# SparkFun_LED_Array_8x7_Charlieplex.net
KiCad netlist of a schematic drawn in EAGLE
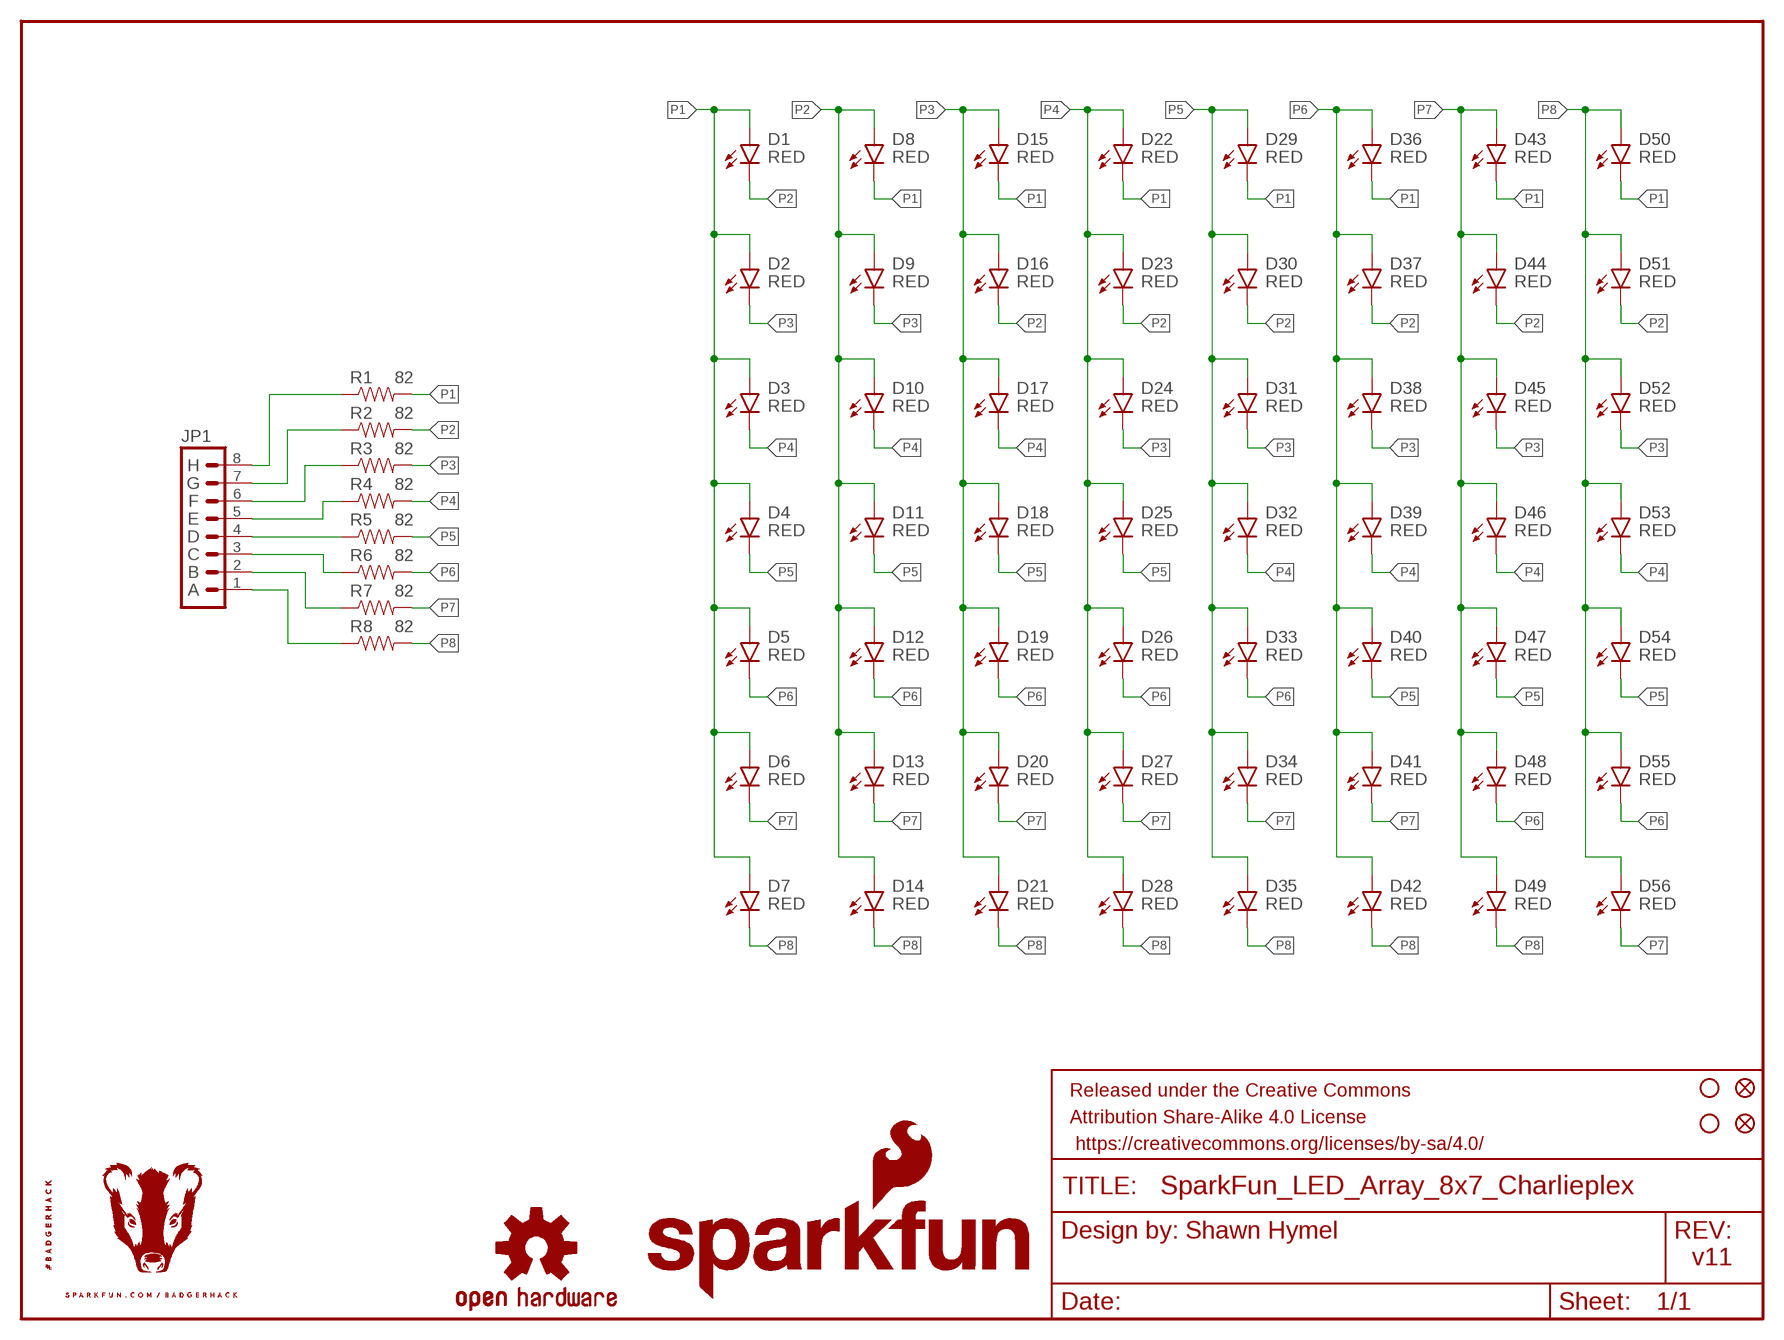
[diagram p0: schematic, sheet 1]

(export (version "E")
  (design (tool "Eeschema 10.0.6"))
  (components
    (comp (ref "D1")
      (value "RED")
      (footprint "eagle-import:LED-0603")
      (libsource (lib "eagle-import") (part "LED-RED0603"))
    )
    (comp (ref "D2")
      (value "RED")
      (footprint "eagle-import:LED-0603")
      (libsource (lib "eagle-import") (part "LED-RED0603"))
    )
    (comp (ref "D3")
      (value "RED")
      (footprint "eagle-import:LED-0603")
      (libsource (lib "eagle-import") (part "LED-RED0603"))
    )
    (comp (ref "D4")
      (value "RED")
      (footprint "eagle-import:LED-0603")
      (libsource (lib "eagle-import") (part "LED-RED0603"))
    )
    (comp (ref "D5")
      (value "RED")
      (footprint "eagle-import:LED-0603")
      (libsource (lib "eagle-import") (part "LED-RED0603"))
    )
    (comp (ref "D6")
      (value "RED")
      (footprint "eagle-import:LED-0603")
      (libsource (lib "eagle-import") (part "LED-RED0603"))
    )
    (comp (ref "D7")
      (value "RED")
      (footprint "eagle-import:LED-0603")
      (libsource (lib "eagle-import") (part "LED-RED0603"))
    )
    (comp (ref "D8")
      (value "RED")
      (footprint "eagle-import:LED-0603")
      (libsource (lib "eagle-import") (part "LED-RED0603"))
    )
    (comp (ref "D9")
      (value "RED")
      (footprint "eagle-import:LED-0603")
      (libsource (lib "eagle-import") (part "LED-RED0603"))
    )
    (comp (ref "D10")
      (value "RED")
      (footprint "eagle-import:LED-0603")
      (libsource (lib "eagle-import") (part "LED-RED0603"))
    )
    (comp (ref "D11")
      (value "RED")
      (footprint "eagle-import:LED-0603")
      (libsource (lib "eagle-import") (part "LED-RED0603"))
    )
    (comp (ref "D12")
      (value "RED")
      (footprint "eagle-import:LED-0603")
      (libsource (lib "eagle-import") (part "LED-RED0603"))
    )
    (comp (ref "D13")
      (value "RED")
      (footprint "eagle-import:LED-0603")
      (libsource (lib "eagle-import") (part "LED-RED0603"))
    )
    (comp (ref "D14")
      (value "RED")
      (footprint "eagle-import:LED-0603")
      (libsource (lib "eagle-import") (part "LED-RED0603"))
    )
    (comp (ref "D15")
      (value "RED")
      (footprint "eagle-import:LED-0603")
      (libsource (lib "eagle-import") (part "LED-RED0603"))
    )
    (comp (ref "D16")
      (value "RED")
      (footprint "eagle-import:LED-0603")
      (libsource (lib "eagle-import") (part "LED-RED0603"))
    )
    (comp (ref "D17")
      (value "RED")
      (footprint "eagle-import:LED-0603")
      (libsource (lib "eagle-import") (part "LED-RED0603"))
    )
    (comp (ref "D18")
      (value "RED")
      (footprint "eagle-import:LED-0603")
      (libsource (lib "eagle-import") (part "LED-RED0603"))
    )
    (comp (ref "D19")
      (value "RED")
      (footprint "eagle-import:LED-0603")
      (libsource (lib "eagle-import") (part "LED-RED0603"))
    )
    (comp (ref "D20")
      (value "RED")
      (footprint "eagle-import:LED-0603")
      (libsource (lib "eagle-import") (part "LED-RED0603"))
    )
    (comp (ref "D21")
      (value "RED")
      (footprint "eagle-import:LED-0603")
      (libsource (lib "eagle-import") (part "LED-RED0603"))
    )
    (comp (ref "D22")
      (value "RED")
      (footprint "eagle-import:LED-0603")
      (libsource (lib "eagle-import") (part "LED-RED0603"))
    )
    (comp (ref "D23")
      (value "RED")
      (footprint "eagle-import:LED-0603")
      (libsource (lib "eagle-import") (part "LED-RED0603"))
    )
    (comp (ref "D24")
      (value "RED")
      (footprint "eagle-import:LED-0603")
      (libsource (lib "eagle-import") (part "LED-RED0603"))
    )
    (comp (ref "D25")
      (value "RED")
      (footprint "eagle-import:LED-0603")
      (libsource (lib "eagle-import") (part "LED-RED0603"))
    )
    (comp (ref "D26")
      (value "RED")
      (footprint "eagle-import:LED-0603")
      (libsource (lib "eagle-import") (part "LED-RED0603"))
    )
    (comp (ref "D27")
      (value "RED")
      (footprint "eagle-import:LED-0603")
      (libsource (lib "eagle-import") (part "LED-RED0603"))
    )
    (comp (ref "D28")
      (value "RED")
      (footprint "eagle-import:LED-0603")
      (libsource (lib "eagle-import") (part "LED-RED0603"))
    )
    (comp (ref "D29")
      (value "RED")
      (footprint "eagle-import:LED-0603")
      (libsource (lib "eagle-import") (part "LED-RED0603"))
    )
    (comp (ref "D30")
      (value "RED")
      (footprint "eagle-import:LED-0603")
      (libsource (lib "eagle-import") (part "LED-RED0603"))
    )
    (comp (ref "D31")
      (value "RED")
      (footprint "eagle-import:LED-0603")
      (libsource (lib "eagle-import") (part "LED-RED0603"))
    )
    (comp (ref "D32")
      (value "RED")
      (footprint "eagle-import:LED-0603")
      (libsource (lib "eagle-import") (part "LED-RED0603"))
    )
    (comp (ref "D33")
      (value "RED")
      (footprint "eagle-import:LED-0603")
      (libsource (lib "eagle-import") (part "LED-RED0603"))
    )
    (comp (ref "D34")
      (value "RED")
      (footprint "eagle-import:LED-0603")
      (libsource (lib "eagle-import") (part "LED-RED0603"))
    )
    (comp (ref "D35")
      (value "RED")
      (footprint "eagle-import:LED-0603")
      (libsource (lib "eagle-import") (part "LED-RED0603"))
    )
    (comp (ref "D36")
      (value "RED")
      (footprint "eagle-import:LED-0603")
      (libsource (lib "eagle-import") (part "LED-RED0603"))
    )
    (comp (ref "D37")
      (value "RED")
      (footprint "eagle-import:LED-0603")
      (libsource (lib "eagle-import") (part "LED-RED0603"))
    )
    (comp (ref "D38")
      (value "RED")
      (footprint "eagle-import:LED-0603")
      (libsource (lib "eagle-import") (part "LED-RED0603"))
    )
    (comp (ref "D39")
      (value "RED")
      (footprint "eagle-import:LED-0603")
      (libsource (lib "eagle-import") (part "LED-RED0603"))
    )
    (comp (ref "D40")
      (value "RED")
      (footprint "eagle-import:LED-0603")
      (libsource (lib "eagle-import") (part "LED-RED0603"))
    )
    (comp (ref "D41")
      (value "RED")
      (footprint "eagle-import:LED-0603")
      (libsource (lib "eagle-import") (part "LED-RED0603"))
    )
    (comp (ref "D42")
      (value "RED")
      (footprint "eagle-import:LED-0603")
      (libsource (lib "eagle-import") (part "LED-RED0603"))
    )
    (comp (ref "D43")
      (value "RED")
      (footprint "eagle-import:LED-0603")
      (libsource (lib "eagle-import") (part "LED-RED0603"))
    )
    (comp (ref "D44")
      (value "RED")
      (footprint "eagle-import:LED-0603")
      (libsource (lib "eagle-import") (part "LED-RED0603"))
    )
    (comp (ref "D45")
      (value "RED")
      (footprint "eagle-import:LED-0603")
      (libsource (lib "eagle-import") (part "LED-RED0603"))
    )
    (comp (ref "D46")
      (value "RED")
      (footprint "eagle-import:LED-0603")
      (libsource (lib "eagle-import") (part "LED-RED0603"))
    )
    (comp (ref "D47")
      (value "RED")
      (footprint "eagle-import:LED-0603")
      (libsource (lib "eagle-import") (part "LED-RED0603"))
    )
    (comp (ref "D48")
      (value "RED")
      (footprint "eagle-import:LED-0603")
      (libsource (lib "eagle-import") (part "LED-RED0603"))
    )
    (comp (ref "D49")
      (value "RED")
      (footprint "eagle-import:LED-0603")
      (libsource (lib "eagle-import") (part "LED-RED0603"))
    )
    (comp (ref "D50")
      (value "RED")
      (footprint "eagle-import:LED-0603")
      (libsource (lib "eagle-import") (part "LED-RED0603"))
    )
    (comp (ref "D51")
      (value "RED")
      (footprint "eagle-import:LED-0603")
      (libsource (lib "eagle-import") (part "LED-RED0603"))
    )
    (comp (ref "D52")
      (value "RED")
      (footprint "eagle-import:LED-0603")
      (libsource (lib "eagle-import") (part "LED-RED0603"))
    )
    (comp (ref "D53")
      (value "RED")
      (footprint "eagle-import:LED-0603")
      (libsource (lib "eagle-import") (part "LED-RED0603"))
    )
    (comp (ref "D54")
      (value "RED")
      (footprint "eagle-import:LED-0603")
      (libsource (lib "eagle-import") (part "LED-RED0603"))
    )
    (comp (ref "D55")
      (value "RED")
      (footprint "eagle-import:LED-0603")
      (libsource (lib "eagle-import") (part "LED-RED0603"))
    )
    (comp (ref "D56")
      (value "RED")
      (footprint "eagle-import:LED-0603")
      (libsource (lib "eagle-import") (part "LED-RED0603"))
    )
    (comp (ref "FID1")
      (value "FIDUCIAL1X2")
      (footprint "eagle-import:FIDUCIAL-1X2")
      (libsource (lib "eagle-import") (part "FIDUCIAL1X2"))
    )
    (comp (ref "FID2")
      (value "FIDUCIAL1X2")
      (footprint "eagle-import:FIDUCIAL-1X2")
      (libsource (lib "eagle-import") (part "FIDUCIAL1X2"))
    )
    (comp (ref "FRAME1")
      (value "FRAME-LETTER")
      (footprint "eagle-import:CREATIVE_COMMONS")
      (fields
        (field (name "DESIGNER") "Shawn Hymel")
        (field (name "VERSION") "v11")
        (field (name "DESIGNER_1") "Shawn Hymel")
        (field (name "VERSION_1") "v11")
      )
      (libsource (lib "eagle-import") (part "FRAME-LETTER"))
    )
    (comp (ref "JP1")
      (value "M08LOCK_NO_SILK")
      (footprint "eagle-import:1X08_LOCK_NO_SILK")
      (libsource (lib "eagle-import") (part "M08LOCK_NO_SILK"))
    )
    (comp (ref "LOGO2")
      (value "OSHW-LOGOS")
      (footprint "eagle-import:OSHW-LOGO-S")
      (libsource (lib "eagle-import") (part "OSHW-LOGOS"))
    )
    (comp (ref "R1")
      (value "82")
      (footprint "eagle-import:0603-RES")
      (libsource (lib "eagle-import") (part "82OHM-1/10W-1%(0603)SMD"))
    )
    (comp (ref "R2")
      (value "82")
      (footprint "eagle-import:0603-RES")
      (libsource (lib "eagle-import") (part "82OHM-1/10W-1%(0603)SMD"))
    )
    (comp (ref "R3")
      (value "82")
      (footprint "eagle-import:0603-RES")
      (libsource (lib "eagle-import") (part "82OHM-1/10W-1%(0603)SMD"))
    )
    (comp (ref "R4")
      (value "82")
      (footprint "eagle-import:0603-RES")
      (libsource (lib "eagle-import") (part "82OHM-1/10W-1%(0603)SMD"))
    )
    (comp (ref "R5")
      (value "82")
      (footprint "eagle-import:0603-RES")
      (libsource (lib "eagle-import") (part "82OHM-1/10W-1%(0603)SMD"))
    )
    (comp (ref "R6")
      (value "82")
      (footprint "eagle-import:0603-RES")
      (libsource (lib "eagle-import") (part "82OHM-1/10W-1%(0603)SMD"))
    )
    (comp (ref "R7")
      (value "82")
      (footprint "eagle-import:0603-RES")
      (libsource (lib "eagle-import") (part "82OHM-1/10W-1%(0603)SMD"))
    )
    (comp (ref "R8")
      (value "82")
      (footprint "eagle-import:0603-RES")
      (libsource (lib "eagle-import") (part "82OHM-1/10W-1%(0603)SMD"))
    )
    (comp (ref "STANDOFF1")
      (value "STAND-OFF")
      (footprint "eagle-import:STAND-OFF")
      (libsource (lib "eagle-import") (part "STAND-OFF"))
    )
    (comp (ref "STANDOFF2")
      (value "STAND-OFF")
      (footprint "eagle-import:STAND-OFF")
      (libsource (lib "eagle-import") (part "STAND-OFF"))
    )
    (comp (ref "U$1")
      (value "SFE_LOGO_NAME_FLAME.1_INCH")
      (footprint "eagle-import:SFE_LOGO_NAME_FLAME_.1")
      (libsource (lib "eagle-import") (part "SFE_LOGO_NAME_FLAME.1_INCH"))
    )
    (comp (ref "U$2")
      (value "BADGERHACK_LOGODUMMY")
      (footprint "eagle-import:DUMMY")
      (libsource (lib "eagle-import") (part "BADGERHACK_LOGODUMMY"))
    )
  )
  (nets
    (net (code "1") (name "Net-(JP1-Pad1)") (class "Default")
      (node (ref "JP1") (pin "1") (pinfunction "1_1") (pintype "passive"))
      (node (ref "R8") (pin "1") (pinfunction "1_1") (pintype "passive"))
    )
    (net (code "2") (name "Net-(JP1-Pad2)") (class "Default")
      (node (ref "JP1") (pin "2") (pinfunction "2_2") (pintype "passive"))
      (node (ref "R7") (pin "1") (pinfunction "1_1") (pintype "passive"))
    )
    (net (code "3") (name "Net-(JP1-Pad3)") (class "Default")
      (node (ref "JP1") (pin "3") (pinfunction "3_3") (pintype "passive"))
      (node (ref "R6") (pin "1") (pinfunction "1_1") (pintype "passive"))
    )
    (net (code "4") (name "Net-(JP1-Pad4)") (class "Default")
      (node (ref "JP1") (pin "4") (pinfunction "4_4") (pintype "passive"))
      (node (ref "R5") (pin "1") (pinfunction "1_1") (pintype "passive"))
    )
    (net (code "5") (name "Net-(JP1-Pad5)") (class "Default")
      (node (ref "JP1") (pin "5") (pinfunction "5_5") (pintype "passive"))
      (node (ref "R4") (pin "1") (pinfunction "1_1") (pintype "passive"))
    )
    (net (code "6") (name "Net-(JP1-Pad6)") (class "Default")
      (node (ref "JP1") (pin "6") (pinfunction "6_6") (pintype "passive"))
      (node (ref "R3") (pin "1") (pinfunction "1_1") (pintype "passive"))
    )
    (net (code "7") (name "Net-(JP1-Pad7)") (class "Default")
      (node (ref "JP1") (pin "7") (pinfunction "7_7") (pintype "passive"))
      (node (ref "R2") (pin "1") (pinfunction "1_1") (pintype "passive"))
    )
    (net (code "8") (name "Net-(JP1-Pad8)") (class "Default")
      (node (ref "JP1") (pin "8") (pinfunction "8_8") (pintype "passive"))
      (node (ref "R1") (pin "1") (pinfunction "1_1") (pintype "passive"))
    )
    (net (code "9") (name "P1") (class "Default")
      (node (ref "D1") (pin "A") (pinfunction "A_A") (pintype "passive"))
      (node (ref "D15") (pin "C") (pinfunction "C_C") (pintype "passive"))
      (node (ref "D2") (pin "A") (pinfunction "A_A") (pintype "passive"))
      (node (ref "D22") (pin "C") (pinfunction "C_C") (pintype "passive"))
      (node (ref "D29") (pin "C") (pinfunction "C_C") (pintype "passive"))
      (node (ref "D3") (pin "A") (pinfunction "A_A") (pintype "passive"))
      (node (ref "D36") (pin "C") (pinfunction "C_C") (pintype "passive"))
      (node (ref "D4") (pin "A") (pinfunction "A_A") (pintype "passive"))
      (node (ref "D43") (pin "C") (pinfunction "C_C") (pintype "passive"))
      (node (ref "D5") (pin "A") (pinfunction "A_A") (pintype "passive"))
      (node (ref "D50") (pin "C") (pinfunction "C_C") (pintype "passive"))
      (node (ref "D6") (pin "A") (pinfunction "A_A") (pintype "passive"))
      (node (ref "D7") (pin "A") (pinfunction "A_A") (pintype "passive"))
      (node (ref "D8") (pin "C") (pinfunction "C_C") (pintype "passive"))
      (node (ref "R1") (pin "2") (pinfunction "2_2") (pintype "passive"))
    )
    (net (code "10") (name "P2") (class "Default")
      (node (ref "D1") (pin "C") (pinfunction "C_C") (pintype "passive"))
      (node (ref "D10") (pin "A") (pinfunction "A_A") (pintype "passive"))
      (node (ref "D11") (pin "A") (pinfunction "A_A") (pintype "passive"))
      (node (ref "D12") (pin "A") (pinfunction "A_A") (pintype "passive"))
      (node (ref "D13") (pin "A") (pinfunction "A_A") (pintype "passive"))
      (node (ref "D14") (pin "A") (pinfunction "A_A") (pintype "passive"))
      (node (ref "D16") (pin "C") (pinfunction "C_C") (pintype "passive"))
      (node (ref "D23") (pin "C") (pinfunction "C_C") (pintype "passive"))
      (node (ref "D30") (pin "C") (pinfunction "C_C") (pintype "passive"))
      (node (ref "D37") (pin "C") (pinfunction "C_C") (pintype "passive"))
      (node (ref "D44") (pin "C") (pinfunction "C_C") (pintype "passive"))
      (node (ref "D51") (pin "C") (pinfunction "C_C") (pintype "passive"))
      (node (ref "D8") (pin "A") (pinfunction "A_A") (pintype "passive"))
      (node (ref "D9") (pin "A") (pinfunction "A_A") (pintype "passive"))
      (node (ref "R2") (pin "2") (pinfunction "2_2") (pintype "passive"))
    )
    (net (code "11") (name "P3") (class "Default")
      (node (ref "D15") (pin "A") (pinfunction "A_A") (pintype "passive"))
      (node (ref "D16") (pin "A") (pinfunction "A_A") (pintype "passive"))
      (node (ref "D17") (pin "A") (pinfunction "A_A") (pintype "passive"))
      (node (ref "D18") (pin "A") (pinfunction "A_A") (pintype "passive"))
      (node (ref "D19") (pin "A") (pinfunction "A_A") (pintype "passive"))
      (node (ref "D2") (pin "C") (pinfunction "C_C") (pintype "passive"))
      (node (ref "D20") (pin "A") (pinfunction "A_A") (pintype "passive"))
      (node (ref "D21") (pin "A") (pinfunction "A_A") (pintype "passive"))
      (node (ref "D24") (pin "C") (pinfunction "C_C") (pintype "passive"))
      (node (ref "D31") (pin "C") (pinfunction "C_C") (pintype "passive"))
      (node (ref "D38") (pin "C") (pinfunction "C_C") (pintype "passive"))
      (node (ref "D45") (pin "C") (pinfunction "C_C") (pintype "passive"))
      (node (ref "D52") (pin "C") (pinfunction "C_C") (pintype "passive"))
      (node (ref "D9") (pin "C") (pinfunction "C_C") (pintype "passive"))
      (node (ref "R3") (pin "2") (pinfunction "2_2") (pintype "passive"))
    )
    (net (code "12") (name "P4") (class "Default")
      (node (ref "D10") (pin "C") (pinfunction "C_C") (pintype "passive"))
      (node (ref "D17") (pin "C") (pinfunction "C_C") (pintype "passive"))
      (node (ref "D22") (pin "A") (pinfunction "A_A") (pintype "passive"))
      (node (ref "D23") (pin "A") (pinfunction "A_A") (pintype "passive"))
      (node (ref "D24") (pin "A") (pinfunction "A_A") (pintype "passive"))
      (node (ref "D25") (pin "A") (pinfunction "A_A") (pintype "passive"))
      (node (ref "D26") (pin "A") (pinfunction "A_A") (pintype "passive"))
      (node (ref "D27") (pin "A") (pinfunction "A_A") (pintype "passive"))
      (node (ref "D28") (pin "A") (pinfunction "A_A") (pintype "passive"))
      (node (ref "D3") (pin "C") (pinfunction "C_C") (pintype "passive"))
      (node (ref "D32") (pin "C") (pinfunction "C_C") (pintype "passive"))
      (node (ref "D39") (pin "C") (pinfunction "C_C") (pintype "passive"))
      (node (ref "D46") (pin "C") (pinfunction "C_C") (pintype "passive"))
      (node (ref "D53") (pin "C") (pinfunction "C_C") (pintype "passive"))
      (node (ref "R4") (pin "2") (pinfunction "2_2") (pintype "passive"))
    )
    (net (code "13") (name "P5") (class "Default")
      (node (ref "D11") (pin "C") (pinfunction "C_C") (pintype "passive"))
      (node (ref "D18") (pin "C") (pinfunction "C_C") (pintype "passive"))
      (node (ref "D25") (pin "C") (pinfunction "C_C") (pintype "passive"))
      (node (ref "D29") (pin "A") (pinfunction "A_A") (pintype "passive"))
      (node (ref "D30") (pin "A") (pinfunction "A_A") (pintype "passive"))
      (node (ref "D31") (pin "A") (pinfunction "A_A") (pintype "passive"))
      (node (ref "D32") (pin "A") (pinfunction "A_A") (pintype "passive"))
      (node (ref "D33") (pin "A") (pinfunction "A_A") (pintype "passive"))
      (node (ref "D34") (pin "A") (pinfunction "A_A") (pintype "passive"))
      (node (ref "D35") (pin "A") (pinfunction "A_A") (pintype "passive"))
      (node (ref "D4") (pin "C") (pinfunction "C_C") (pintype "passive"))
      (node (ref "D40") (pin "C") (pinfunction "C_C") (pintype "passive"))
      (node (ref "D47") (pin "C") (pinfunction "C_C") (pintype "passive"))
      (node (ref "D54") (pin "C") (pinfunction "C_C") (pintype "passive"))
      (node (ref "R5") (pin "2") (pinfunction "2_2") (pintype "passive"))
    )
    (net (code "14") (name "P6") (class "Default")
      (node (ref "D12") (pin "C") (pinfunction "C_C") (pintype "passive"))
      (node (ref "D19") (pin "C") (pinfunction "C_C") (pintype "passive"))
      (node (ref "D26") (pin "C") (pinfunction "C_C") (pintype "passive"))
      (node (ref "D33") (pin "C") (pinfunction "C_C") (pintype "passive"))
      (node (ref "D36") (pin "A") (pinfunction "A_A") (pintype "passive"))
      (node (ref "D37") (pin "A") (pinfunction "A_A") (pintype "passive"))
      (node (ref "D38") (pin "A") (pinfunction "A_A") (pintype "passive"))
      (node (ref "D39") (pin "A") (pinfunction "A_A") (pintype "passive"))
      (node (ref "D40") (pin "A") (pinfunction "A_A") (pintype "passive"))
      (node (ref "D41") (pin "A") (pinfunction "A_A") (pintype "passive"))
      (node (ref "D42") (pin "A") (pinfunction "A_A") (pintype "passive"))
      (node (ref "D48") (pin "C") (pinfunction "C_C") (pintype "passive"))
      (node (ref "D5") (pin "C") (pinfunction "C_C") (pintype "passive"))
      (node (ref "D55") (pin "C") (pinfunction "C_C") (pintype "passive"))
      (node (ref "R6") (pin "2") (pinfunction "2_2") (pintype "passive"))
    )
    (net (code "15") (name "P7") (class "Default")
      (node (ref "D13") (pin "C") (pinfunction "C_C") (pintype "passive"))
      (node (ref "D20") (pin "C") (pinfunction "C_C") (pintype "passive"))
      (node (ref "D27") (pin "C") (pinfunction "C_C") (pintype "passive"))
      (node (ref "D34") (pin "C") (pinfunction "C_C") (pintype "passive"))
      (node (ref "D41") (pin "C") (pinfunction "C_C") (pintype "passive"))
      (node (ref "D43") (pin "A") (pinfunction "A_A") (pintype "passive"))
      (node (ref "D44") (pin "A") (pinfunction "A_A") (pintype "passive"))
      (node (ref "D45") (pin "A") (pinfunction "A_A") (pintype "passive"))
      (node (ref "D46") (pin "A") (pinfunction "A_A") (pintype "passive"))
      (node (ref "D47") (pin "A") (pinfunction "A_A") (pintype "passive"))
      (node (ref "D48") (pin "A") (pinfunction "A_A") (pintype "passive"))
      (node (ref "D49") (pin "A") (pinfunction "A_A") (pintype "passive"))
      (node (ref "D56") (pin "C") (pinfunction "C_C") (pintype "passive"))
      (node (ref "D6") (pin "C") (pinfunction "C_C") (pintype "passive"))
      (node (ref "R7") (pin "2") (pinfunction "2_2") (pintype "passive"))
    )
    (net (code "16") (name "P8") (class "Default")
      (node (ref "D14") (pin "C") (pinfunction "C_C") (pintype "passive"))
      (node (ref "D21") (pin "C") (pinfunction "C_C") (pintype "passive"))
      (node (ref "D28") (pin "C") (pinfunction "C_C") (pintype "passive"))
      (node (ref "D35") (pin "C") (pinfunction "C_C") (pintype "passive"))
      (node (ref "D42") (pin "C") (pinfunction "C_C") (pintype "passive"))
      (node (ref "D49") (pin "C") (pinfunction "C_C") (pintype "passive"))
      (node (ref "D50") (pin "A") (pinfunction "A_A") (pintype "passive"))
      (node (ref "D51") (pin "A") (pinfunction "A_A") (pintype "passive"))
      (node (ref "D52") (pin "A") (pinfunction "A_A") (pintype "passive"))
      (node (ref "D53") (pin "A") (pinfunction "A_A") (pintype "passive"))
      (node (ref "D54") (pin "A") (pinfunction "A_A") (pintype "passive"))
      (node (ref "D55") (pin "A") (pinfunction "A_A") (pintype "passive"))
      (node (ref "D56") (pin "A") (pinfunction "A_A") (pintype "passive"))
      (node (ref "D7") (pin "C") (pinfunction "C_C") (pintype "passive"))
      (node (ref "R8") (pin "2") (pinfunction "2_2") (pintype "passive"))
    )
  )
)
